# 10-Click.net
KiCad netlist of a schematic drawn in Altium Designer
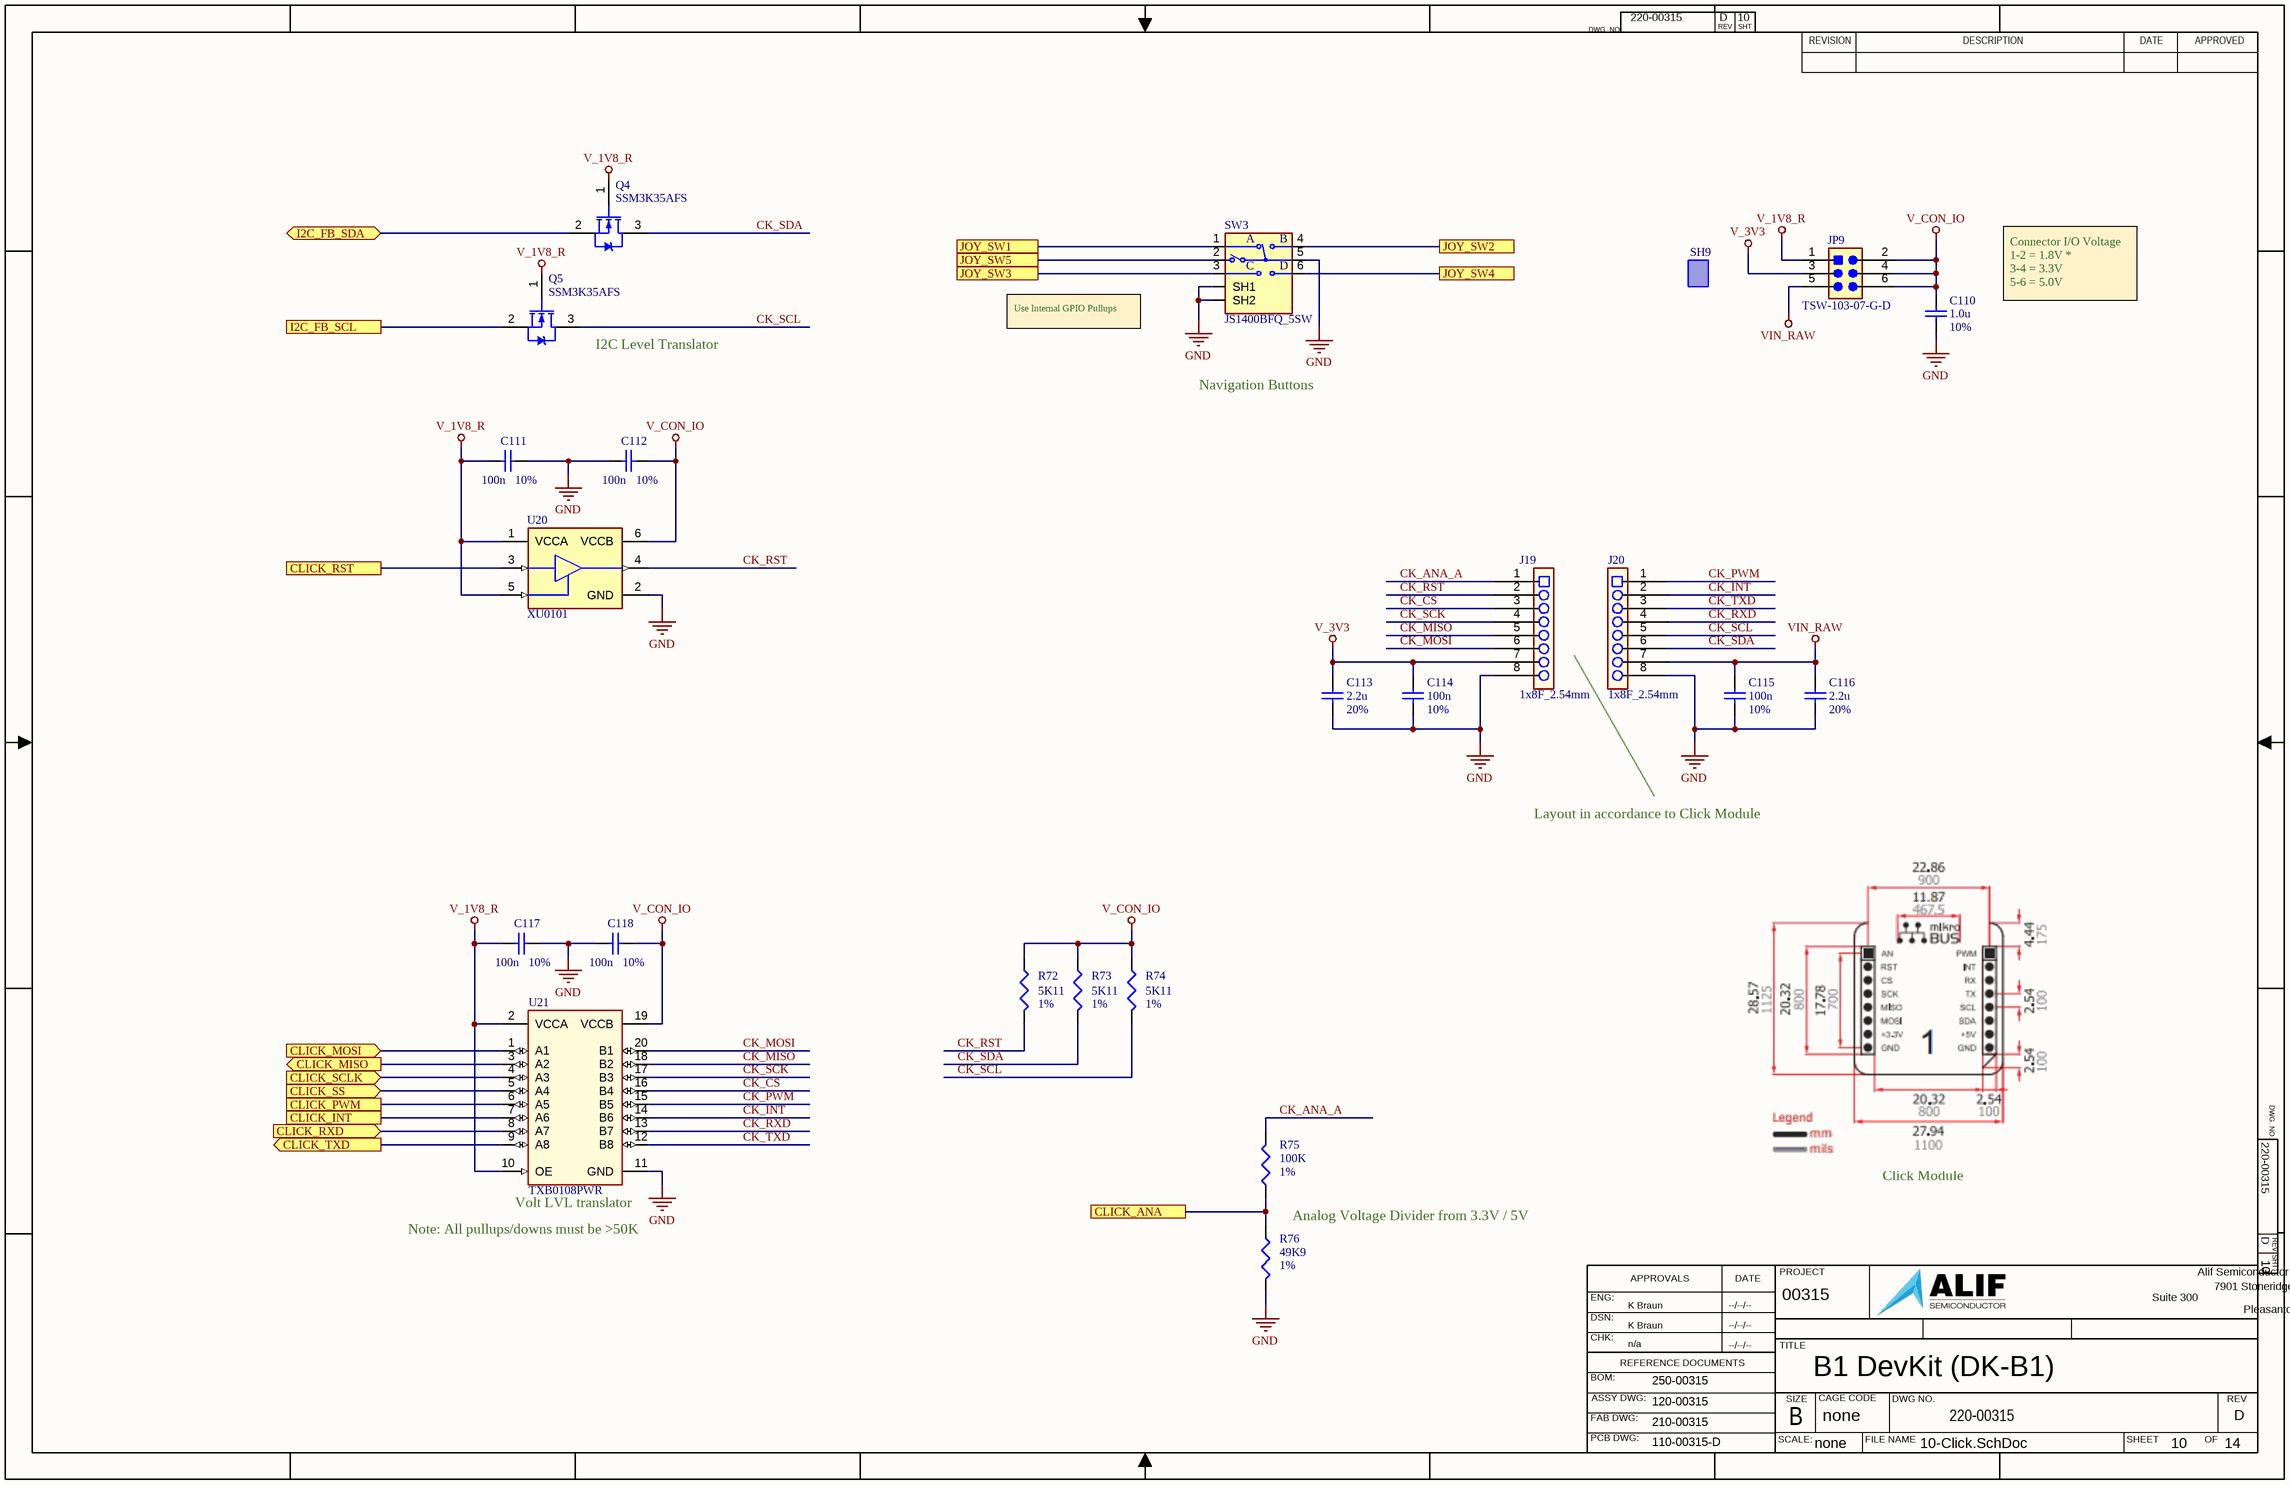
[diagram p0: 10-Click.SchDoc]

(export (version "E")
  (design (tool "Eeschema 10.0.6"))
  (components
    (comp (ref "C110")
      (value "1.0u")
      (footprint "CAPC0402-01")
      (description "Cap,1.0uF,20%,25V,X5R,0402")
      (fields
        (field (name "VOLTAGE") "25V")
        (field (name "TOLERANCE") "10%")
        (field (name "Comment") "Cap")
        (field (name "PUBLISHER") "Altium Limited")
      )
      (libsource (lib "kb1") (part "Cap"))
    )
    (comp (ref "C111")
      (value "100n")
      (footprint "CAPC0402-01")
      (description "Cap,100nF,10%,50V,X7R,0402")
      (fields
        (field (name "VOLTAGE") "50V")
        (field (name "TOLERANCE") "10%")
        (field (name "Comment") "Cap")
        (field (name "PUBLISHER") "Altium Limited")
      )
      (libsource (lib "kb1") (part "Cap"))
    )
    (comp (ref "C112")
      (value "100n")
      (footprint "CAPC0402-01")
      (description "Cap,100nF,10%,50V,X7R,0402")
      (fields
        (field (name "VOLTAGE") "50V")
        (field (name "TOLERANCE") "10%")
        (field (name "Comment") "Cap")
        (field (name "PUBLISHER") "Altium Limited")
      )
      (libsource (lib "kb1") (part "Cap"))
    )
    (comp (ref "C113")
      (value "2.2u")
      (footprint "CAPC0402-01")
      (description "Cap,2.2uF,20%,25V,X5R,0402")
      (fields
        (field (name "VOLTAGE") "25V")
        (field (name "TOLERANCE") "20%")
        (field (name "Comment") "Cap_225M25VX5R0402_1")
        (field (name "PUBLISHER") "Altium Limited")
      )
      (libsource (lib "Alif-2") (part "Cap_225M25VX5R0402_1"))
    )
    (comp (ref "C114")
      (value "100n")
      (footprint "CAPC0402-01")
      (description "Cap,100nF,10%,50V,X7R,0402")
      (fields
        (field (name "VOLTAGE") "50V")
        (field (name "TOLERANCE") "10%")
        (field (name "Comment") "Cap")
        (field (name "PUBLISHER") "Altium Limited")
      )
      (libsource (lib "kb1") (part "Cap"))
    )
    (comp (ref "C115")
      (value "100n")
      (footprint "CAPC0402-01")
      (description "Cap,100nF,10%,50V,X7R,0402")
      (fields
        (field (name "VOLTAGE") "50V")
        (field (name "TOLERANCE") "10%")
        (field (name "Comment") "Cap")
        (field (name "PUBLISHER") "Altium Limited")
      )
      (libsource (lib "kb1") (part "Cap"))
    )
    (comp (ref "C116")
      (value "2.2u")
      (footprint "CAPC0402-01")
      (description "Cap,2.2uF,20%,25V,X5R,0402")
      (fields
        (field (name "VOLTAGE") "25V")
        (field (name "TOLERANCE") "20%")
        (field (name "Comment") "Cap_225M25VX5R0402_1")
        (field (name "PUBLISHER") "Altium Limited")
      )
      (libsource (lib "Alif-2") (part "Cap_225M25VX5R0402_1"))
    )
    (comp (ref "C117")
      (value "100n")
      (footprint "CAPC0402-01")
      (description "Cap,100nF,10%,50V,X7R,0402")
      (fields
        (field (name "VOLTAGE") "50V")
        (field (name "TOLERANCE") "10%")
        (field (name "Comment") "Cap")
        (field (name "PUBLISHER") "Altium Limited")
      )
      (libsource (lib "kb1") (part "Cap"))
    )
    (comp (ref "C118")
      (value "100n")
      (footprint "CAPC0402-01")
      (description "Cap,100nF,10%,50V,X7R,0402")
      (fields
        (field (name "VOLTAGE") "50V")
        (field (name "TOLERANCE") "10%")
        (field (name "Comment") "Cap")
        (field (name "PUBLISHER") "Altium Limited")
      )
      (libsource (lib "kb1") (part "Cap"))
    )
    (comp (ref "J19")
      (value "1x8F_2.54mm")
      (footprint "RHDR8W80P0X254_1X8_2082X254X850P")
      (description "Hdr,Female,1x8,2.54mm,Strt,Unshrouded")
      (fields (field (name "Comment") "Hdr_F_1x8_2.5MM_STRT_UNSH_1"))
      (libsource (lib "") (part "Hdr_F_1x8_2.5MM_STRT_UNSH_1_1"))
    )
    (comp (ref "J20")
      (value "1x8F_2.54mm")
      (footprint "RHDR8W80P0X254_1X8_2082X254X850P")
      (description "Hdr,Female,1x8,2.54mm,Strt,Unshrouded")
      (fields (field (name "Comment") "Hdr_F_1x8_2.5MM_STRT_UNSH_1"))
      (libsource (lib "Alif-2") (part "Hdr_F_1x8_2.5MM_STRT_UNSH_1"))
    )
    (comp (ref "JP9")
      (value "TSW-103-07-G-D")
      (footprint "HDRV6W64P254_2X3_762X508X838P")
      (description "Hdr, Male,2x3, 2.54mm,0.230mate,0.100-0.120post,, Strt")
      (libsource (lib "Alif-2") (part "Hdr_M_2X3_2M54_STRT_UNSHROUDED"))
    )
    (comp (ref "Q4")
      (value "NMOS-2_SOT")
      (footprint "SC75_SSM_TOS-L")
      (description "MOSFET,N-CH,20V,250mA,1.1Ohm,SOT-23")
      (fields
        (field (name "MANUFACTURER PART NUMBER 1") "SSM3K35AFS")
        (field (name "PUBLISHER") "Altium Limited")
      )
      (libsource (lib "Alif-2") (part "NMOS-2_SOT"))
    )
    (comp (ref "Q5")
      (value "NMOS-2_SOT")
      (footprint "SC75_SSM_TOS-L")
      (description "MOSFET,N-CH,20V,250mA,1.1Ohm,SOT-23")
      (fields
        (field (name "MANUFACTURER PART NUMBER 1") "SSM3K35AFS")
        (field (name "PUBLISHER") "Altium Limited")
      )
      (libsource (lib "Alif-2") (part "NMOS-2_SOT"))
    )
    (comp (ref "R72")
      (value "5K11")
      (footprint "RESC0402-01")
      (description "Res,5K11,1%,100ppm,0402")
      (fields
        (field (name "TOLERANCE") "1%")
        (field (name "Comment") "Res3")
        (field (name "PUBLISHER") "Altium Limited")
      )
      (libsource (lib "kb1") (part "Res3"))
    )
    (comp (ref "R73")
      (value "5K11")
      (footprint "RESC0402-01")
      (description "Res,5K11,1%,100ppm,0402")
      (fields
        (field (name "TOLERANCE") "1%")
        (field (name "Comment") "Res3")
        (field (name "PUBLISHER") "Altium Limited")
      )
      (libsource (lib "kb1") (part "Res3"))
    )
    (comp (ref "R74")
      (value "5K11")
      (footprint "RESC0402-01")
      (description "Res,5K11,1%,100ppm,0402")
      (fields
        (field (name "TOLERANCE") "1%")
        (field (name "Comment") "Res3")
        (field (name "PUBLISHER") "Altium Limited")
      )
      (libsource (lib "kb1") (part "Res3"))
    )
    (comp (ref "R75")
      (value "100K")
      (footprint "RESC0402-01")
      (description "Res,100K,1%,100ppm,0402")
      (fields
        (field (name "TOLERANCE") "1%")
        (field (name "Comment") "Res3")
        (field (name "PUBLISHER") "Altium Limited")
      )
      (libsource (lib "kb1") (part "Res3"))
    )
    (comp (ref "R76")
      (value "49K9")
      (footprint "RESC0402-01")
      (description "Res,49K9,1%,100ppm,0402")
      (fields
        (field (name "TOLERANCE") "1%")
        (field (name "Comment") "Res3")
        (field (name "PUBLISHER") "Altium Limited")
      )
      (libsource (lib "kb1") (part "Res3"))
    )
    (comp (ref "SH9")
      (value "Shunt")
      (description "Shunt,Female,1x2,2.54mm,Gold,Strt")
      (libsource (lib "Alif-2") (part "SHUNT_F_1x2_2.5MM_STRT"))
    )
    (comp (ref "SW3")
      (value "JS1400BFQ_5SW")
      (footprint "SW_JS1400BFQ")
      (description "Navigation Switch, 2 - Axis Digital (Mechanical Switch) Output")
      (fields (field (name "MF") "E-Switch") (field (name "DIGI-KEY_PART_NUMBER") "EG5858-ND"))
      (libsource (lib "Alif-2") (part "JS1400BFQ_5SW"))
    )
    (comp (ref "U20")
      (value "XU0101")
      (footprint "SOT363_TI")
      (libsource (lib "Alif2") (part "IC_XLAT_TXU0101DCKR"))
    )
    (comp (ref "U21")
      (value "TXB0108PWR")
      (footprint "TSSOP20_TI_PW0020A_M")
      (libsource (lib "Alif-2") (part "IC_XLAT_TXB0108PWR"))
    )
  )
  (nets
    (net (code "1") (name "/CK_ANA_A") (class "Default")
      (node (ref "J19") (pin "1") (pinfunction "1_1") (pintype "passive"))
      (node (ref "R75") (pin "2") (pinfunction "2_2") (pintype "passive"))
    )
    (net (code "2") (name "/CK_CS") (class "Default")
      (node (ref "J19") (pin "3") (pinfunction "3_3") (pintype "passive"))
      (node (ref "U21") (pin "16") (pinfunction "B4_16") (pintype "bidirectional"))
    )
    (net (code "3") (name "/CK_INT") (class "Default")
      (node (ref "J20") (pin "2") (pinfunction "2_2") (pintype "passive"))
      (node (ref "U21") (pin "14") (pinfunction "B6_14") (pintype "bidirectional"))
    )
    (net (code "4") (name "/CK_MISO") (class "Default")
      (node (ref "J19") (pin "5") (pinfunction "5_5") (pintype "passive"))
      (node (ref "U21") (pin "18") (pinfunction "B2_18") (pintype "bidirectional"))
    )
    (net (code "5") (name "/CK_MOSI") (class "Default")
      (node (ref "J19") (pin "6") (pinfunction "6_6") (pintype "passive"))
      (node (ref "U21") (pin "20") (pinfunction "B1_20") (pintype "bidirectional"))
    )
    (net (code "6") (name "/CK_PWM") (class "Default")
      (node (ref "J20") (pin "1") (pinfunction "1_1") (pintype "passive"))
      (node (ref "U21") (pin "15") (pinfunction "B5_15") (pintype "bidirectional"))
    )
    (net (code "7") (name "/CK_RST") (class "Default")
      (node (ref "J19") (pin "2") (pinfunction "2_2") (pintype "passive"))
      (node (ref "R72") (pin "2") (pinfunction "2_2") (pintype "passive"))
      (node (ref "U20") (pin "4") (pinfunction "BY_4") (pintype "output"))
    )
    (net (code "8") (name "/CK_RXD") (class "Default")
      (node (ref "J20") (pin "4") (pinfunction "4_4") (pintype "passive"))
      (node (ref "U21") (pin "13") (pinfunction "B7_13") (pintype "bidirectional"))
    )
    (net (code "9") (name "/CK_SCK") (class "Default")
      (node (ref "J19") (pin "4") (pinfunction "4_4") (pintype "passive"))
      (node (ref "U21") (pin "17") (pinfunction "B3_17") (pintype "bidirectional"))
    )
    (net (code "10") (name "/CK_SCL") (class "Default")
      (node (ref "J20") (pin "5") (pinfunction "5_5") (pintype "passive"))
      (node (ref "Q5") (pin "3") (pinfunction "D_3") (pintype "passive"))
      (node (ref "R74") (pin "2") (pinfunction "2_2") (pintype "passive"))
    )
    (net (code "11") (name "/CK_SDA") (class "Default")
      (node (ref "J20") (pin "6") (pinfunction "6_6") (pintype "passive"))
      (node (ref "Q4") (pin "3") (pinfunction "D_3") (pintype "passive"))
      (node (ref "R73") (pin "2") (pinfunction "2_2") (pintype "passive"))
    )
    (net (code "12") (name "/CK_TXD") (class "Default")
      (node (ref "J20") (pin "3") (pinfunction "3_3") (pintype "passive"))
      (node (ref "U21") (pin "12") (pinfunction "B8_12") (pintype "bidirectional"))
    )
    (net (code "13") (name "/CLICK_ANA") (class "Default")
      (node (ref "R75") (pin "1") (pinfunction "1_1") (pintype "passive"))
      (node (ref "R76") (pin "1") (pinfunction "1_1") (pintype "passive"))
    )
    (net (code "14") (name "/CLICK_INT") (class "Default")
      (node (ref "U21") (pin "7") (pinfunction "A6_7") (pintype "bidirectional"))
    )
    (net (code "15") (name "/CLICK_MISO") (class "Default")
      (node (ref "U21") (pin "3") (pinfunction "A2_3") (pintype "bidirectional"))
    )
    (net (code "16") (name "/CLICK_MOSI") (class "Default")
      (node (ref "U21") (pin "1") (pinfunction "A1_1") (pintype "bidirectional"))
    )
    (net (code "17") (name "/CLICK_PWM") (class "Default")
      (node (ref "U21") (pin "6") (pinfunction "A5_6") (pintype "bidirectional"))
    )
    (net (code "18") (name "/CLICK_RST") (class "Default")
      (node (ref "U20") (pin "3") (pinfunction "A_3") (pintype "input"))
    )
    (net (code "19") (name "/CLICK_RXD") (class "Default")
      (node (ref "U21") (pin "8") (pinfunction "A7_8") (pintype "bidirectional"))
    )
    (net (code "20") (name "/CLICK_SCLK") (class "Default")
      (node (ref "U21") (pin "4") (pinfunction "A3_4") (pintype "bidirectional"))
    )
    (net (code "21") (name "/CLICK_SS") (class "Default")
      (node (ref "U21") (pin "5") (pinfunction "A4_5") (pintype "bidirectional"))
    )
    (net (code "22") (name "/CLICK_TXD") (class "Default")
      (node (ref "U21") (pin "9") (pinfunction "A8_9") (pintype "bidirectional"))
    )
    (net (code "23") (name "/I2C_FB_SCL") (class "Default")
      (node (ref "Q5") (pin "2") (pinfunction "S_2") (pintype "passive"))
    )
    (net (code "24") (name "/I2C_FB_SDA") (class "Default")
      (node (ref "Q4") (pin "2") (pinfunction "S_2") (pintype "passive"))
    )
    (net (code "25") (name "/JOY_SW1") (class "Default")
      (node (ref "SW3") (pin "1") (pinfunction "A_1") (pintype "passive"))
    )
    (net (code "26") (name "/JOY_SW2") (class "Default")
      (node (ref "SW3") (pin "4") (pinfunction "B_4") (pintype "passive"))
    )
    (net (code "27") (name "/JOY_SW3") (class "Default")
      (node (ref "SW3") (pin "3") (pinfunction "C_3") (pintype "passive"))
    )
    (net (code "28") (name "/JOY_SW4") (class "Default")
      (node (ref "SW3") (pin "6") (pinfunction "D_6") (pintype "passive"))
    )
    (net (code "29") (name "/JOY_SW5") (class "Default")
      (node (ref "SW3") (pin "2") (pinfunction "E_2") (pintype "passive"))
    )
    (net (code "30") (name "GND") (class "Default")
      (node (ref "C110") (pin "1") (pinfunction "1_1") (pintype "passive"))
      (node (ref "C111") (pin "1") (pinfunction "1_1") (pintype "passive"))
      (node (ref "C112") (pin "2") (pinfunction "2_2") (pintype "passive"))
      (node (ref "C113") (pin "1") (pinfunction "1_1") (pintype "passive"))
      (node (ref "C114") (pin "1") (pinfunction "1_1") (pintype "passive"))
      (node (ref "C115") (pin "1") (pinfunction "1_1") (pintype "passive"))
      (node (ref "C116") (pin "1") (pinfunction "1_1") (pintype "passive"))
      (node (ref "C117") (pin "1") (pinfunction "1_1") (pintype "passive"))
      (node (ref "C118") (pin "2") (pinfunction "2_2") (pintype "passive"))
      (node (ref "J19") (pin "8") (pinfunction "8_8") (pintype "passive"))
      (node (ref "J20") (pin "8") (pinfunction "8_8") (pintype "passive"))
      (node (ref "R76") (pin "2") (pinfunction "2_2") (pintype "passive"))
      (node (ref "SW3") (pin "5") (pinfunction "COM_5") (pintype "passive"))
      (node (ref "SW3") (pin "SH1") (pinfunction "SH1_SH1") (pintype "passive"))
      (node (ref "SW3") (pin "SH2") (pinfunction "SH2_SH2") (pintype "passive"))
      (node (ref "U20") (pin "2") (pinfunction "GND_2") (pintype "power_in"))
      (node (ref "U21") (pin "11") (pinfunction "GND_11") (pintype "power_in"))
    )
    (net (code "31") (name "VIN_RAW") (class "Default")
      (node (ref "C115") (pin "2") (pinfunction "2_2") (pintype "passive"))
      (node (ref "C116") (pin "2") (pinfunction "2_2") (pintype "passive"))
      (node (ref "J20") (pin "7") (pinfunction "7_7") (pintype "passive"))
      (node (ref "JP9") (pin "5") (pinfunction "5_5") (pintype "passive"))
    )
    (net (code "32") (name "V_1V8_R") (class "Default")
      (node (ref "C111") (pin "2") (pinfunction "2_2") (pintype "passive"))
      (node (ref "C117") (pin "2") (pinfunction "2_2") (pintype "passive"))
      (node (ref "JP9") (pin "1") (pinfunction "1_1") (pintype "passive"))
      (node (ref "Q4") (pin "1") (pinfunction "G_1") (pintype "passive"))
      (node (ref "Q5") (pin "1") (pinfunction "G_1") (pintype "passive"))
      (node (ref "U20") (pin "1") (pinfunction "VCCA_1") (pintype "power_in"))
      (node (ref "U20") (pin "5") (pinfunction "OE_5") (pintype "input"))
      (node (ref "U21") (pin "10") (pinfunction "OE_10") (pintype "input"))
      (node (ref "U21") (pin "2") (pinfunction "VCCA_2") (pintype "power_in"))
    )
    (net (code "33") (name "V_3V3") (class "Default")
      (node (ref "C113") (pin "2") (pinfunction "2_2") (pintype "passive"))
      (node (ref "C114") (pin "2") (pinfunction "2_2") (pintype "passive"))
      (node (ref "J19") (pin "7") (pinfunction "7_7") (pintype "passive"))
      (node (ref "JP9") (pin "3") (pinfunction "3_3") (pintype "passive"))
    )
    (net (code "34") (name "V_CON_IO") (class "Default")
      (node (ref "C110") (pin "2") (pinfunction "2_2") (pintype "passive"))
      (node (ref "C112") (pin "1") (pinfunction "1_1") (pintype "passive"))
      (node (ref "C118") (pin "1") (pinfunction "1_1") (pintype "passive"))
      (node (ref "JP9") (pin "2") (pinfunction "2_2") (pintype "passive"))
      (node (ref "JP9") (pin "4") (pinfunction "4_4") (pintype "passive"))
      (node (ref "JP9") (pin "6") (pinfunction "6_6") (pintype "passive"))
      (node (ref "R72") (pin "1") (pinfunction "1_1") (pintype "passive"))
      (node (ref "R73") (pin "1") (pinfunction "1_1") (pintype "passive"))
      (node (ref "R74") (pin "1") (pinfunction "1_1") (pintype "passive"))
      (node (ref "U20") (pin "6") (pinfunction "VCCB_6") (pintype "power_in"))
      (node (ref "U21") (pin "19") (pinfunction "VCCB_19") (pintype "power_in"))
    )
  )
)
